# user_input.net
KiCad netlist of a schematic drawn in Altium Designer
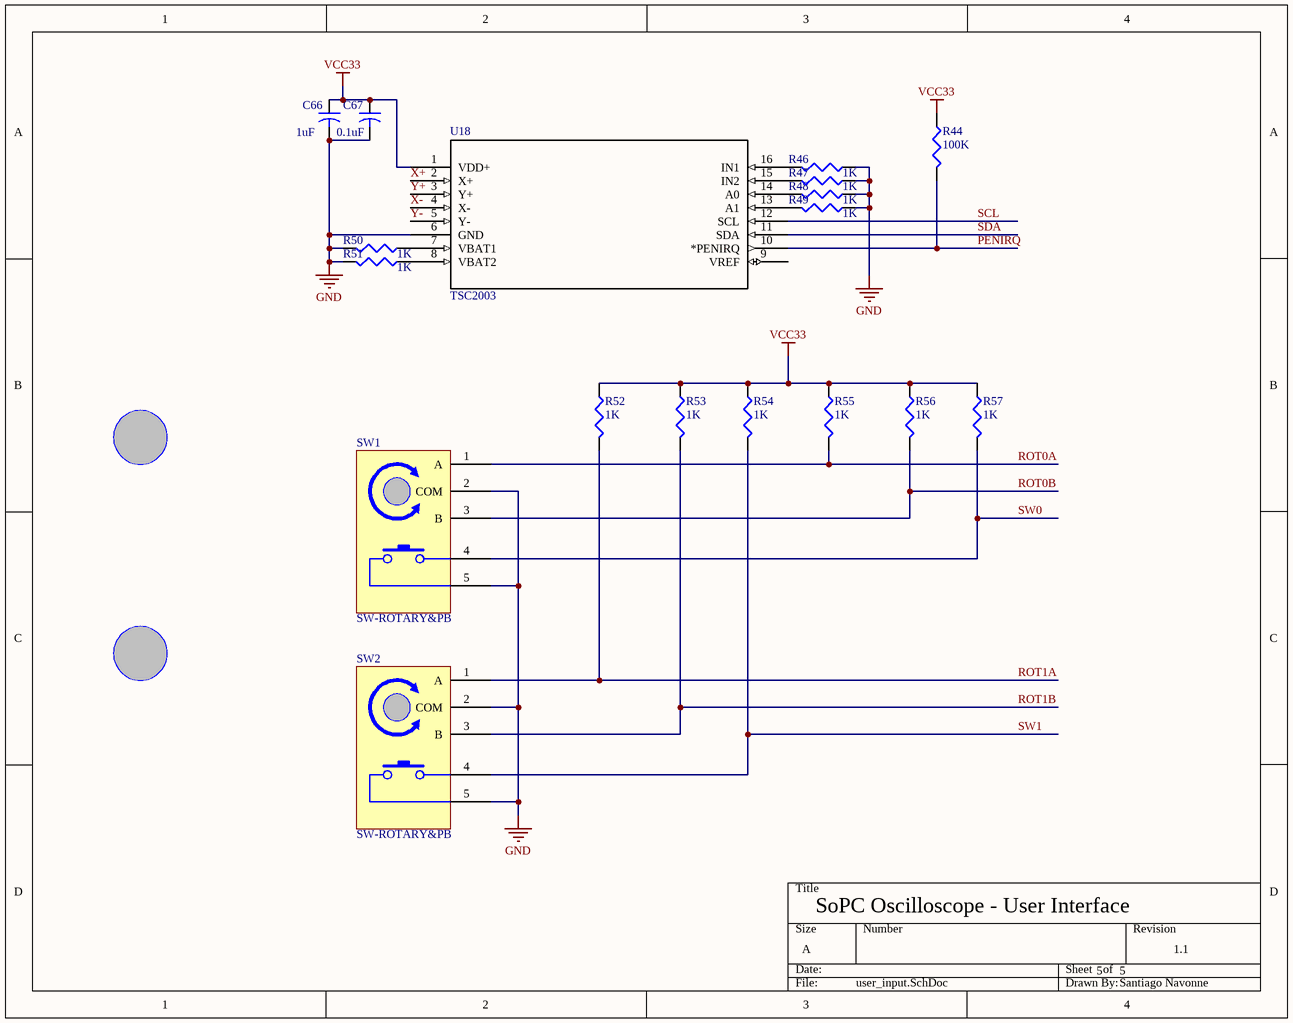
[diagram p0: user_input.SchDoc]

(export (version "E")
  (design (tool "Eeschema 10.0.6"))
  (components
    (comp (ref "C66")
      (value "1uF")
      (footprint "CAPC1608L")
      (description "Capacitor")
      (fields (field (name "Comment") "Cap2") (field (name "PUBLISHER") "Altium Limited"))
      (libsource (lib "Miscellaneous Devices") (part "Cap2"))
    )
    (comp (ref "C67")
      (value "0.1uF")
      (footprint "CAPC1608L")
      (description "Capacitor")
      (fields (field (name "Comment") "Cap2") (field (name "PUBLISHER") "Altium Limited"))
      (libsource (lib "Miscellaneous Devices") (part "Cap2"))
    )
    (comp (ref "R44")
      (value "100K")
      (footprint "RESC1608N")
      (description "Resistor")
      (fields (field (name "Comment") "Res3") (field (name "PUBLISHER") "Altium Limited"))
      (libsource (lib "Miscellaneous Devices") (part "Res3"))
    )
    (comp (ref "R46")
      (value "1K")
      (footprint "RESC1608N")
      (description "Resistor")
      (fields (field (name "Comment") "Res3") (field (name "PUBLISHER") "Altium Limited"))
      (libsource (lib "Miscellaneous Devices") (part "Res3"))
    )
    (comp (ref "R47")
      (value "1K")
      (footprint "RESC1608N")
      (description "Resistor")
      (fields (field (name "Comment") "Res3") (field (name "PUBLISHER") "Altium Limited"))
      (libsource (lib "Miscellaneous Devices") (part "Res3"))
    )
    (comp (ref "R48")
      (value "1K")
      (footprint "RESC1608N")
      (description "Resistor")
      (fields (field (name "Comment") "Res3") (field (name "PUBLISHER") "Altium Limited"))
      (libsource (lib "Miscellaneous Devices") (part "Res3"))
    )
    (comp (ref "R49")
      (value "1K")
      (footprint "RESC1608N")
      (description "Resistor")
      (fields (field (name "Comment") "Res3") (field (name "PUBLISHER") "Altium Limited"))
      (libsource (lib "Miscellaneous Devices") (part "Res3"))
    )
    (comp (ref "R50")
      (value "1K")
      (footprint "RESC1608N")
      (description "Resistor")
      (fields (field (name "Comment") "Res3") (field (name "PUBLISHER") "Altium Limited"))
      (libsource (lib "Miscellaneous Devices") (part "Res3"))
    )
    (comp (ref "R51")
      (value "1K")
      (footprint "RESC1608N")
      (description "Resistor")
      (fields (field (name "Comment") "Res3") (field (name "PUBLISHER") "Altium Limited"))
      (libsource (lib "Miscellaneous Devices") (part "Res3"))
    )
    (comp (ref "R52")
      (value "1K")
      (footprint "RESC1608N")
      (description "Resistor")
      (fields (field (name "Comment") "Res3") (field (name "PUBLISHER") "Altium Limited"))
      (libsource (lib "Miscellaneous Devices") (part "Res3"))
    )
    (comp (ref "R53")
      (value "1K")
      (footprint "RESC1608N")
      (description "Resistor")
      (fields (field (name "Comment") "Res3") (field (name "PUBLISHER") "Altium Limited"))
      (libsource (lib "Miscellaneous Devices") (part "Res3"))
    )
    (comp (ref "R54")
      (value "1K")
      (footprint "RESC1608N")
      (description "Resistor")
      (fields (field (name "Comment") "Res3") (field (name "PUBLISHER") "Altium Limited"))
      (libsource (lib "Miscellaneous Devices") (part "Res3"))
    )
    (comp (ref "R55")
      (value "1K")
      (footprint "RESC1608N")
      (description "Resistor")
      (fields (field (name "Comment") "Res3") (field (name "PUBLISHER") "Altium Limited"))
      (libsource (lib "Miscellaneous Devices") (part "Res3"))
    )
    (comp (ref "R56")
      (value "1K")
      (footprint "RESC1608N")
      (description "Resistor")
      (fields (field (name "Comment") "Res3") (field (name "PUBLISHER") "Altium Limited"))
      (libsource (lib "Miscellaneous Devices") (part "Res3"))
    )
    (comp (ref "R57")
      (value "1K")
      (footprint "RESC1608N")
      (description "Resistor")
      (fields (field (name "Comment") "Res3") (field (name "PUBLISHER") "Altium Limited"))
      (libsource (lib "Miscellaneous Devices") (part "Res3"))
    )
    (comp (ref "SW1")
      (value "SW-ROTARY&PB")
      (footprint "PEC16-4xxxF-Sxxxx")
      (description "Rotary Encoder with Built-In Push Button")
      (libsource (lib "EECS5X") (part "SW-ROTARY&PB"))
    )
    (comp (ref "SW2")
      (value "SW-ROTARY&PB")
      (footprint "PEC16-4xxxF-Sxxxx")
      (description "Rotary Encoder with Built-In Push Button")
      (libsource (lib "EECS5X") (part "SW-ROTARY&PB"))
    )
    (comp (ref "U18")
      (value "TSC2003")
      (footprint "PW16")
      (description "Imported")
      (fields (field (name "MANUFACTURER") "Texas Instruments"))
      (libsource (lib "2014-02-05_22-29-57") (part "TSC2003_PW_16"))
    )
  )
  (nets
    (net (code "1") (name "/PENIRQ") (class "Default")
      (node (ref "R44") (pin "2") (pinfunction "2_2") (pintype "passive"))
      (node (ref "U18") (pin "10") (pinfunction "*PENIRQ_10") (pintype "output"))
    )
    (net (code "2") (name "/ROT0A") (class "Default")
      (node (ref "R55") (pin "2") (pinfunction "2_2") (pintype "passive"))
      (node (ref "SW1") (pin "1") (pinfunction "A_1") (pintype "passive"))
    )
    (net (code "3") (name "/ROT0B") (class "Default")
      (node (ref "R56") (pin "2") (pinfunction "2_2") (pintype "passive"))
      (node (ref "SW1") (pin "3") (pinfunction "B_3") (pintype "passive"))
    )
    (net (code "4") (name "/ROT1A") (class "Default")
      (node (ref "R52") (pin "2") (pinfunction "2_2") (pintype "passive"))
      (node (ref "SW2") (pin "1") (pinfunction "A_1") (pintype "passive"))
    )
    (net (code "5") (name "/ROT1B") (class "Default")
      (node (ref "R53") (pin "2") (pinfunction "2_2") (pintype "passive"))
      (node (ref "SW2") (pin "3") (pinfunction "B_3") (pintype "passive"))
    )
    (net (code "6") (name "/SCL") (class "Default")
      (node (ref "U18") (pin "12") (pinfunction "SCL_12") (pintype "input"))
    )
    (net (code "7") (name "/SDA") (class "Default")
      (node (ref "U18") (pin "11") (pinfunction "SDA_11") (pintype "input"))
    )
    (net (code "8") (name "/SW0") (class "Default")
      (node (ref "R57") (pin "2") (pinfunction "2_2") (pintype "passive"))
      (node (ref "SW1") (pin "4") (pintype "passive"))
    )
    (net (code "9") (name "/SW1") (class "Default")
      (node (ref "R54") (pin "2") (pinfunction "2_2") (pintype "passive"))
      (node (ref "SW2") (pin "4") (pintype "passive"))
    )
    (net (code "10") (name "/X+") (class "Default")
      (node (ref "U18") (pin "2") (pinfunction "X+_2") (pintype "input"))
    )
    (net (code "11") (name "/X-") (class "Default")
      (node (ref "U18") (pin "4") (pinfunction "X-_4") (pintype "input"))
    )
    (net (code "12") (name "/Y+") (class "Default")
      (node (ref "U18") (pin "3") (pinfunction "Y+_3") (pintype "input"))
    )
    (net (code "13") (name "/Y-") (class "Default")
      (node (ref "U18") (pin "5") (pinfunction "Y-_5") (pintype "input"))
    )
    (net (code "14") (name "GND") (class "Default")
      (node (ref "C66") (pin "2") (pinfunction "2_2") (pintype "passive"))
      (node (ref "C67") (pin "2") (pinfunction "2_2") (pintype "passive"))
      (node (ref "R46") (pin "1") (pinfunction "1_1") (pintype "passive"))
      (node (ref "R47") (pin "1") (pinfunction "1_1") (pintype "passive"))
      (node (ref "R48") (pin "1") (pinfunction "1_1") (pintype "passive"))
      (node (ref "R49") (pin "1") (pinfunction "1_1") (pintype "passive"))
      (node (ref "R50") (pin "2") (pinfunction "2_2") (pintype "passive"))
      (node (ref "R51") (pin "2") (pinfunction "2_2") (pintype "passive"))
      (node (ref "SW1") (pin "2") (pinfunction "COM_2") (pintype "passive"))
      (node (ref "SW1") (pin "5") (pintype "passive"))
      (node (ref "SW2") (pin "2") (pinfunction "COM_2") (pintype "passive"))
      (node (ref "SW2") (pin "5") (pintype "passive"))
      (node (ref "U18") (pin "6") (pinfunction "GND_6") (pintype "power_in"))
    )
    (net (code "15") (name "Net-(U18-A0)") (class "Default")
      (node (ref "R48") (pin "2") (pinfunction "2_2") (pintype "passive"))
      (node (ref "U18") (pin "14") (pinfunction "A0_14") (pintype "input"))
    )
    (net (code "16") (name "Net-(U18-A1)") (class "Default")
      (node (ref "R49") (pin "2") (pinfunction "2_2") (pintype "passive"))
      (node (ref "U18") (pin "13") (pinfunction "A1_13") (pintype "input"))
    )
    (net (code "17") (name "Net-(U18-IN1)") (class "Default")
      (node (ref "R46") (pin "2") (pinfunction "2_2") (pintype "passive"))
      (node (ref "U18") (pin "16") (pinfunction "IN1_16") (pintype "input"))
    )
    (net (code "18") (name "Net-(U18-IN2)") (class "Default")
      (node (ref "R47") (pin "2") (pinfunction "2_2") (pintype "passive"))
      (node (ref "U18") (pin "15") (pinfunction "IN2_15") (pintype "input"))
    )
    (net (code "19") (name "Net-(U18-VBAT1)") (class "Default")
      (node (ref "R50") (pin "1") (pinfunction "1_1") (pintype "passive"))
      (node (ref "U18") (pin "7") (pinfunction "VBAT1_7") (pintype "input"))
    )
    (net (code "20") (name "Net-(U18-VBAT2)") (class "Default")
      (node (ref "R51") (pin "1") (pinfunction "1_1") (pintype "passive"))
      (node (ref "U18") (pin "8") (pinfunction "VBAT2_8") (pintype "input"))
    )
    (net (code "21") (name "VCC33") (class "Default")
      (node (ref "C66") (pin "1") (pinfunction "1_1") (pintype "passive"))
      (node (ref "C67") (pin "1") (pinfunction "1_1") (pintype "passive"))
      (node (ref "R44") (pin "1") (pinfunction "1_1") (pintype "passive"))
      (node (ref "R52") (pin "1") (pinfunction "1_1") (pintype "passive"))
      (node (ref "R53") (pin "1") (pinfunction "1_1") (pintype "passive"))
      (node (ref "R54") (pin "1") (pinfunction "1_1") (pintype "passive"))
      (node (ref "R55") (pin "1") (pinfunction "1_1") (pintype "passive"))
      (node (ref "R56") (pin "1") (pinfunction "1_1") (pintype "passive"))
      (node (ref "R57") (pin "1") (pinfunction "1_1") (pintype "passive"))
      (node (ref "U18") (pin "1") (pinfunction "VDD+_1") (pintype "power_in"))
    )
    (net (code "22") (name "unconnected-(U18-VREF-Pad9)") (class "Default")
      (node (ref "U18") (pin "9") (pinfunction "VREF_9") (pintype "bidirectional"))
    )
  )
)
